# Zio_Qwiic_RGB_LED.net
KiCad netlist of a schematic drawn in EAGLE
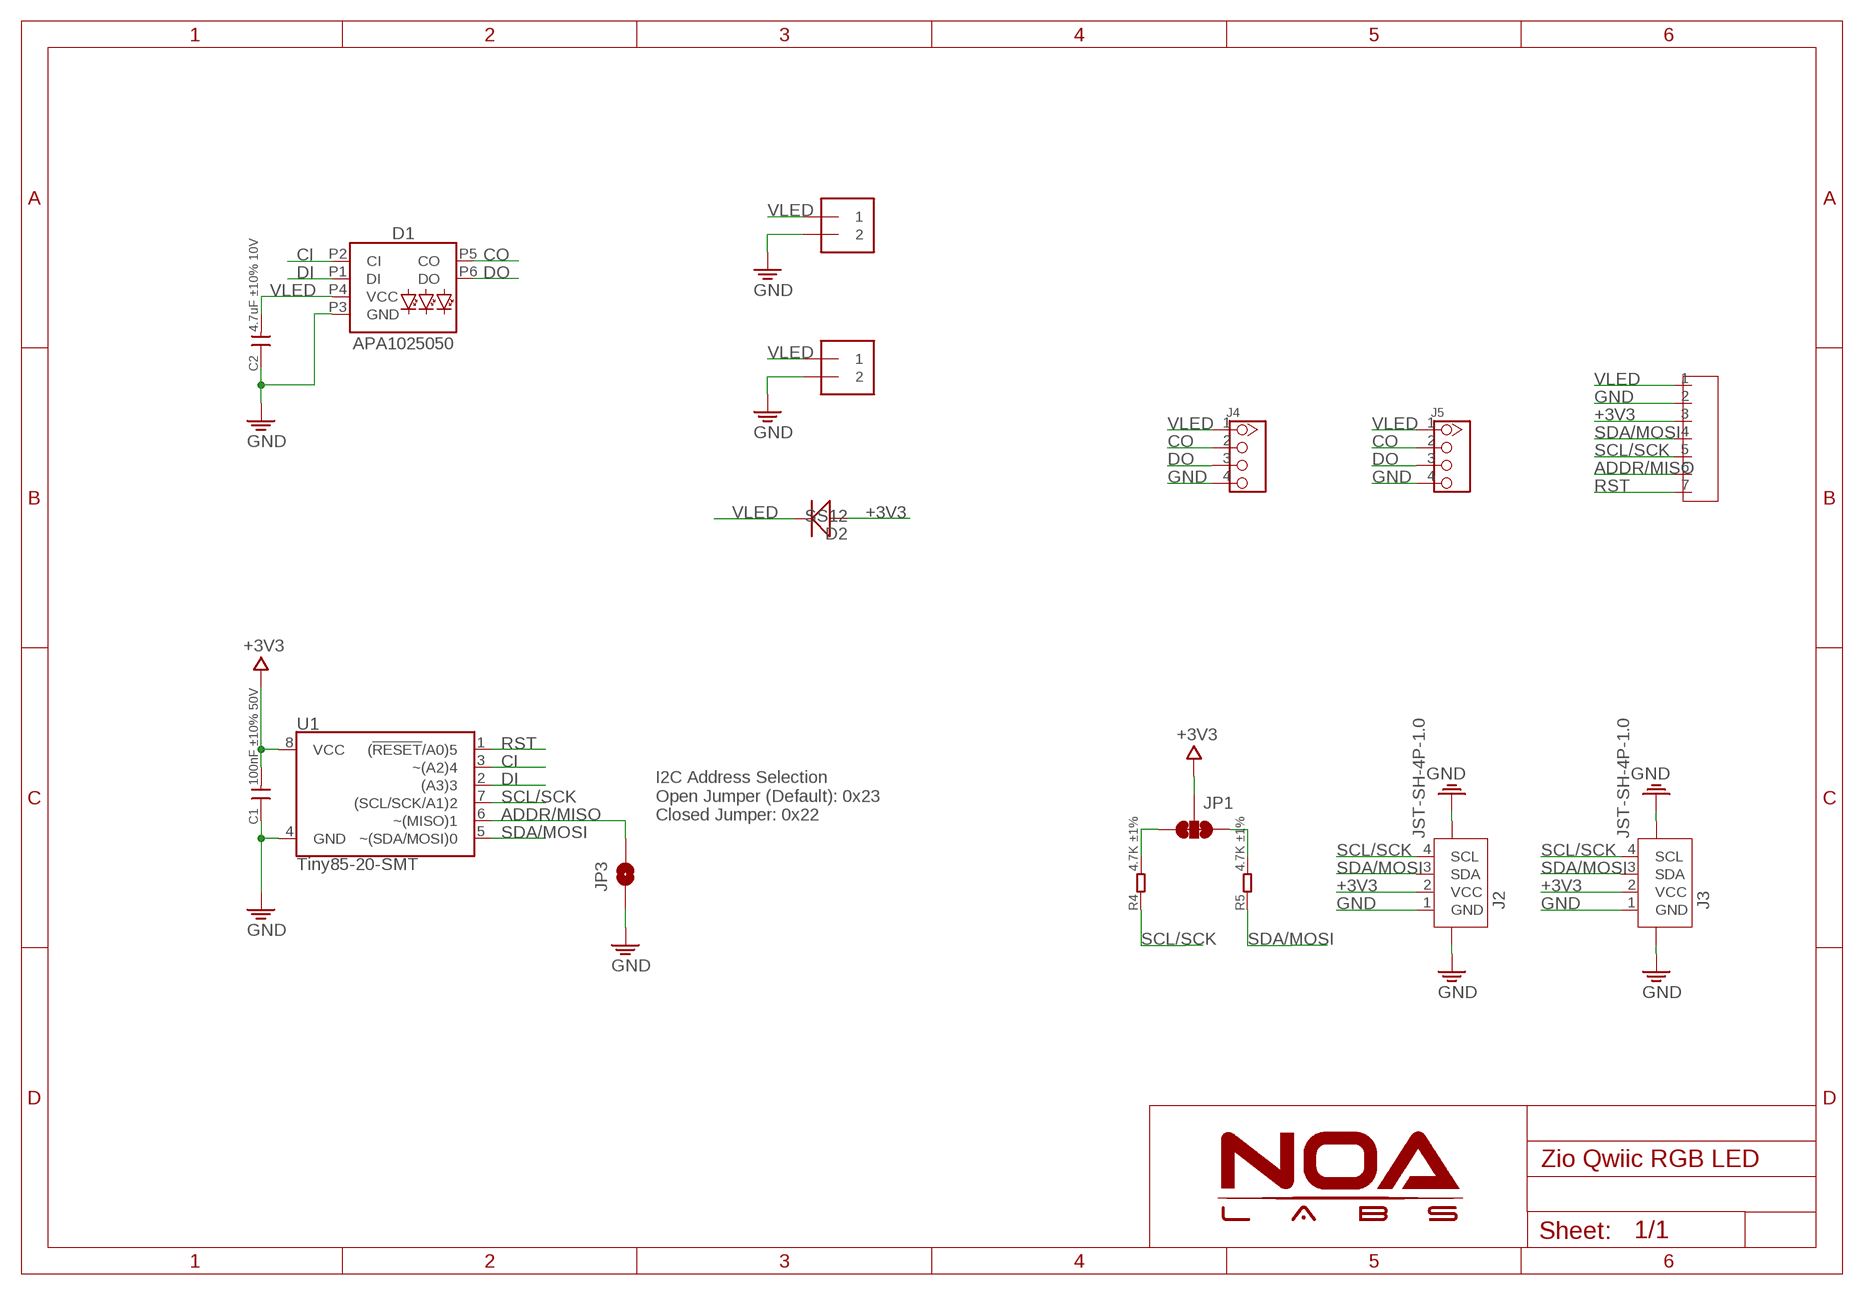
[diagram p0: schematic, sheet 1]

(export (version "E")
  (design (tool "Eeschema 10.0.6"))
  (components
    (comp (ref "C1")
      (value "100nF ±10% 50V")
      (footprint "eagle-import:C0402")
      (libsource (lib "eagle-import") (part "C-0402"))
    )
    (comp (ref "C2")
      (value "4.7uF ±10% 10V")
      (footprint "eagle-import:C0603")
      (libsource (lib "eagle-import") (part "C-0603"))
    )
    (comp (ref "D1")
      (value "APA1025050")
      (footprint "eagle-import:APA102-5050")
      (libsource (lib "eagle-import") (part "APA1025050"))
    )
    (comp (ref "D2")
      (value "SS12")
      (footprint "eagle-import:DO-214AC")
      (libsource (lib "eagle-import") (part "D214AA"))
    )
    (comp (ref "J1")
      (value "HEADER-7P-2.54")
      (footprint "eagle-import:7P-2.54-65_35MIL")
      (libsource (lib "eagle-import") (part "HEADER-7P-2.54"))
    )
    (comp (ref "J2")
      (value "JST-SH-4P-1.0")
      (footprint "eagle-import:JST-SH-4P")
      (libsource (lib "eagle-import") (part "JST-SH-4P-1.0"))
    )
    (comp (ref "J3")
      (value "JST-SH-4P-1.0")
      (footprint "eagle-import:JST-SH-4P")
      (libsource (lib "eagle-import") (part "JST-SH-4P-1.0"))
    )
    (comp (ref "J4")
      (value "HEADER-4P-2.54-M")
      (footprint "eagle-import:4P-2.54-SMD-M")
      (libsource (lib "eagle-import") (part "HEADER-4P-2.54-M"))
    )
    (comp (ref "J5")
      (value "HEADER-4P-60/35MIL")
      (footprint "eagle-import:4P-65_35MIL")
      (libsource (lib "eagle-import") (part "Connector_NOA_1982094_HEADER-4P-60/35MIL"))
    )
    (comp (ref "J6")
      (value "TERMBLOCK_1X2-3.5MM")
      (footprint "eagle-import:1X2-3.5MM")
      (libsource (lib "eagle-import") (part "TERMBLOCK_1X2-3.5MM"))
    )
    (comp (ref "J7")
      (value "TERMBLOCK_1X2-3.5MM")
      (footprint "eagle-import:1X2-3.5MM")
      (libsource (lib "eagle-import") (part "TERMBLOCK_1X2-3.5MM"))
    )
    (comp (ref "JP1")
      (value "SMT-JUMPER_3_2-NC_TRACE")
      (footprint "eagle-import:SMT-JUMPER_3_2-NC_TRACE")
      (libsource (lib "eagle-import") (part "SMT-JUMPER_3_2-NC_TRACE"))
    )
    (comp (ref "JP3")
      (value "JUMPER-SMT_2_NC_PASTE_SILK")
      (footprint "eagle-import:SMT-JUMPER_2_NC_PASTE_SILK")
      (libsource (lib "eagle-import") (part "JUMPER-SMT_2_NC_PASTE_SILK"))
    )
    (comp (ref "R4")
      (value "4.7K ±1%")
      (footprint "eagle-import:R0402")
      (libsource (lib "eagle-import") (part "R-0402"))
    )
    (comp (ref "R5")
      (value "4.7K ±1%")
      (footprint "eagle-import:R0402")
      (libsource (lib "eagle-import") (part "R-0402"))
    )
    (comp (ref "U1")
      (value "Tiny85-20-SMT")
      (footprint "eagle-import:SO08-EIAJ_MCU")
      (libsource (lib "eagle-import") (part "ATTINY85-ARDUINOTINY85-20-SMT"))
    )
  )
  (nets
    (net (code "1") (name "+3V3") (class "Default")
      (node (ref "C1") (pin "2") (pinfunction "2_2") (pintype "passive"))
      (node (ref "D2") (pin "A") (pinfunction "+_A") (pintype "passive"))
      (node (ref "J1") (pin "3") (pinfunction "P$3_3") (pintype "bidirectional"))
      (node (ref "J2") (pin "2") (pinfunction "VCC_2") (pintype "bidirectional"))
      (node (ref "J3") (pin "2") (pinfunction "VCC_2") (pintype "bidirectional"))
      (node (ref "JP1") (pin "2") (pinfunction "2_2") (pintype "passive"))
      (node (ref "U1") (pin "8") (pinfunction "VCC_8") (pintype "bidirectional"))
    )
    (net (code "2") (name "/ADDR{slash}MISO") (class "Default")
      (node (ref "J1") (pin "6") (pinfunction "P$6_6") (pintype "bidirectional"))
      (node (ref "JP3") (pin "2") (pinfunction "2_2") (pintype "passive"))
      (node (ref "U1") (pin "6") (pinfunction "~{(MISO})1_6") (pintype "bidirectional"))
    )
    (net (code "3") (name "/CI") (class "Default")
      (node (ref "D1") (pin "P2") (pinfunction "CI_P2") (pintype "bidirectional"))
      (node (ref "U1") (pin "3") (pinfunction "~{(A2})4_3") (pintype "bidirectional"))
    )
    (net (code "4") (name "/CO") (class "Default")
      (node (ref "D1") (pin "P5") (pinfunction "CO_P5") (pintype "bidirectional"))
      (node (ref "J4") (pin "2") (pinfunction "P$2_2") (pintype "bidirectional"))
      (node (ref "J5") (pin "2") (pinfunction "P$2_2") (pintype "bidirectional"))
    )
    (net (code "5") (name "/DI") (class "Default")
      (node (ref "D1") (pin "P1") (pinfunction "DI_P1") (pintype "bidirectional"))
      (node (ref "U1") (pin "2") (pinfunction "(A3)3_2") (pintype "bidirectional"))
    )
    (net (code "6") (name "/DO") (class "Default")
      (node (ref "D1") (pin "P6") (pinfunction "DO_P6") (pintype "bidirectional"))
      (node (ref "J4") (pin "3") (pinfunction "P$3_3") (pintype "bidirectional"))
      (node (ref "J5") (pin "3") (pinfunction "P$3_3") (pintype "bidirectional"))
    )
    (net (code "7") (name "/RST") (class "Default")
      (node (ref "J1") (pin "7") (pinfunction "P$7_7") (pintype "bidirectional"))
      (node (ref "U1") (pin "1") (pinfunction "(~{RESET}/A0)5_1") (pintype "bidirectional"))
    )
    (net (code "8") (name "/SCL{slash}SCK") (class "Default")
      (node (ref "J1") (pin "5") (pinfunction "P$5_5") (pintype "bidirectional"))
      (node (ref "J2") (pin "4") (pinfunction "SCL_4") (pintype "bidirectional"))
      (node (ref "J3") (pin "4") (pinfunction "SCL_4") (pintype "bidirectional"))
      (node (ref "R4") (pin "1") (pinfunction "1_1") (pintype "passive"))
      (node (ref "U1") (pin "7") (pinfunction "(SCL/SCK/A1)2_7") (pintype "bidirectional"))
    )
    (net (code "9") (name "/SDA{slash}MOSI") (class "Default")
      (node (ref "J1") (pin "4") (pinfunction "P$4_4") (pintype "bidirectional"))
      (node (ref "J2") (pin "3") (pinfunction "SDA_3") (pintype "bidirectional"))
      (node (ref "J3") (pin "3") (pinfunction "SDA_3") (pintype "bidirectional"))
      (node (ref "R5") (pin "1") (pinfunction "1_1") (pintype "passive"))
      (node (ref "U1") (pin "5") (pinfunction "~{(SDA/MOSI})0_5") (pintype "bidirectional"))
    )
    (net (code "10") (name "/VLED") (class "Default")
      (node (ref "C2") (pin "2") (pinfunction "2_2") (pintype "passive"))
      (node (ref "D1") (pin "P4") (pinfunction "VCC_P4") (pintype "bidirectional"))
      (node (ref "D2") (pin "C") (pinfunction "-_C") (pintype "passive"))
      (node (ref "J1") (pin "1") (pinfunction "P$1_1") (pintype "bidirectional"))
      (node (ref "J4") (pin "1") (pinfunction "P$1_1") (pintype "bidirectional"))
      (node (ref "J5") (pin "1") (pinfunction "P$1_1") (pintype "bidirectional"))
      (node (ref "J6") (pin "1") (pinfunction "1_1") (pintype "passive"))
      (node (ref "J7") (pin "1") (pinfunction "1_1") (pintype "passive"))
    )
    (net (code "11") (name "GND") (class "Default")
      (node (ref "C1") (pin "1") (pinfunction "1_1") (pintype "passive"))
      (node (ref "C2") (pin "1") (pinfunction "1_1") (pintype "passive"))
      (node (ref "D1") (pin "P3") (pinfunction "GND_P3") (pintype "bidirectional"))
      (node (ref "J1") (pin "2") (pinfunction "P$2_2") (pintype "bidirectional"))
      (node (ref "J2") (pin "1") (pinfunction "GND_1") (pintype "bidirectional"))
      (node (ref "J2") (pin "NC1") (pinfunction "5_NC1") (pintype "bidirectional"))
      (node (ref "J2") (pin "NC2") (pinfunction "6_NC2") (pintype "bidirectional"))
      (node (ref "J3") (pin "1") (pinfunction "GND_1") (pintype "bidirectional"))
      (node (ref "J3") (pin "NC1") (pinfunction "5_NC1") (pintype "bidirectional"))
      (node (ref "J3") (pin "NC2") (pinfunction "6_NC2") (pintype "bidirectional"))
      (node (ref "J4") (pin "4") (pinfunction "P$4_4") (pintype "bidirectional"))
      (node (ref "J5") (pin "4") (pinfunction "P$4_4") (pintype "bidirectional"))
      (node (ref "J6") (pin "2") (pinfunction "2_2") (pintype "passive"))
      (node (ref "J7") (pin "2") (pinfunction "2_2") (pintype "passive"))
      (node (ref "JP3") (pin "1") (pinfunction "1_1") (pintype "passive"))
      (node (ref "U1") (pin "4") (pinfunction "GND_4") (pintype "bidirectional"))
    )
    (net (code "12") (name "Net-(JP1-Pad1)") (class "Default")
      (node (ref "JP1") (pin "1") (pinfunction "1_1") (pintype "passive"))
      (node (ref "R5") (pin "2") (pinfunction "2_2") (pintype "passive"))
    )
    (net (code "13") (name "Net-(JP1-Pad3)") (class "Default")
      (node (ref "JP1") (pin "3") (pinfunction "3_3") (pintype "passive"))
      (node (ref "R4") (pin "2") (pinfunction "2_2") (pintype "passive"))
    )
  )
)
